# Fri3D_2018_POWER_00.net
KiCad netlist of a schematic drawn in Altium Designer
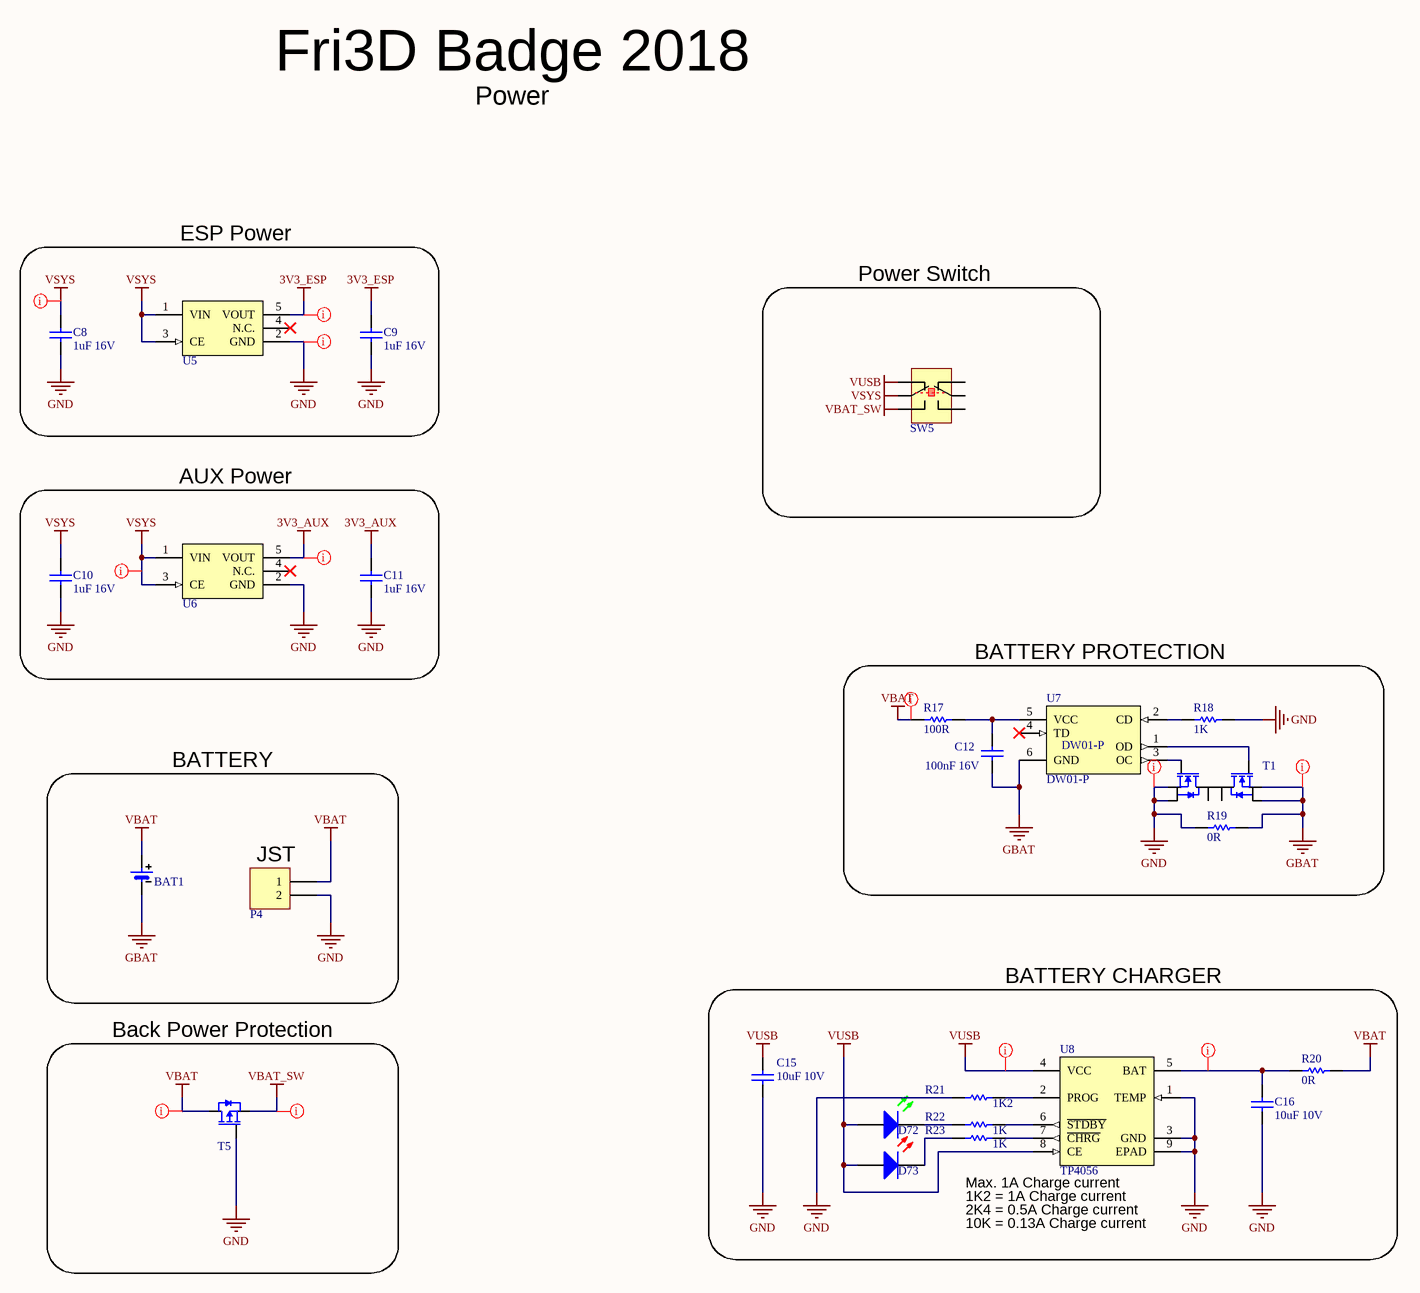
[diagram p0: Fri3D_2018_POWER_00.SchDoc]

(export (version "E")
  (design (tool "Eeschema 10.0.6"))
  (components
    (comp (ref "BAT1")
      (value "18650 Battery holder")
      (footprint "MPD_BH-18650-PC")
      (description "=Description")
      (libsource (lib "Phyx_Components") (part "BAT_2"))
    )
    (comp (ref "C8")
      (value "1uF 16V")
      (footprint "C0603_N")
      (description "Capacitor Ceramic")
      (fields (field (name "Comment") "CAP_CERAMIC"))
      (libsource (lib "Phyx_Components") (part "CAP_CERAMIC"))
    )
    (comp (ref "C9")
      (value "1uF 16V")
      (footprint "C0603_N")
      (description "Capacitor Ceramic")
      (fields (field (name "Comment") "CAP_CERAMIC"))
      (libsource (lib "Phyx_Components") (part "CAP_CERAMIC"))
    )
    (comp (ref "C10")
      (value "1uF 16V")
      (footprint "C0603_N")
      (description "Capacitor Ceramic")
      (fields (field (name "Comment") "CAP_CERAMIC"))
      (libsource (lib "Phyx_Components") (part "CAP_CERAMIC"))
    )
    (comp (ref "C11")
      (value "1uF 16V")
      (footprint "C0603_N")
      (description "Capacitor Ceramic")
      (fields (field (name "Comment") "CAP_CERAMIC"))
      (libsource (lib "Phyx_Components") (part "CAP_CERAMIC"))
    )
    (comp (ref "C12")
      (value "100nF 16V")
      (footprint "C0603_N")
      (description "Capacitor Ceramic")
      (libsource (lib "Phyx_Components") (part "CAP_CERAMIC"))
    )
    (comp (ref "C15")
      (value "10uF 10V")
      (footprint "C0805_N")
      (description "Capacitor Ceramic")
      (fields (field (name "Comment") "CAP_CERAMIC"))
      (libsource (lib "Phyx_Components") (part "CAP_CERAMIC"))
    )
    (comp (ref "C16")
      (value "10uF 10V")
      (footprint "C0805_N")
      (description "Capacitor Ceramic")
      (fields (field (name "Comment") "CAP_CERAMIC"))
      (libsource (lib "Phyx_Components") (part "CAP_CERAMIC"))
    )
    (comp (ref "D72")
      (value "Default 0805 Green LED")
      (footprint "LED_0805_GR")
      (description "=Description")
      (libsource (lib "Phyx_Components") (part "LED_GREEN"))
    )
    (comp (ref "D73")
      (value "Default 0805 Red LED")
      (footprint "LED_0805_RD")
      (description "=Description")
      (libsource (lib "Phyx_Components") (part "LED_RED"))
    )
    (comp (ref "P4")
      (value "Header 2.0mm Shrouded 2")
      (footprint "WE_620102131822")
      (libsource (lib "Phyx_Components") (part "Header 2"))
    )
    (comp (ref "R17")
      (value "100R")
      (footprint "R0603_N")
      (fields (field (name "Comment") "RESISTOR"))
      (libsource (lib "Phyx_Components") (part "RESISTOR"))
    )
    (comp (ref "R18")
      (value "1K")
      (footprint "R0603_N")
      (libsource (lib "Phyx_Components") (part "RESISTOR"))
    )
    (comp (ref "R19")
      (value "0R")
      (footprint "R0603_N")
      (libsource (lib "Phyx_Components") (part "RESISTOR"))
    )
    (comp (ref "R20")
      (value "0R")
      (footprint "R0603_N")
      (libsource (lib "Phyx_Components") (part "RESISTOR"))
    )
    (comp (ref "R21")
      (value "1K2")
      (footprint "R0603_N")
      (fields (field (name "Comment") "RESISTOR"))
      (libsource (lib "Phyx_Components") (part "RESISTOR"))
    )
    (comp (ref "R22")
      (value "1K")
      (footprint "R0603_N")
      (libsource (lib "Phyx_Components") (part "RESISTOR"))
    )
    (comp (ref "R23")
      (value "1K")
      (footprint "R0603_N")
      (libsource (lib "Phyx_Components") (part "RESISTOR"))
    )
    (comp (ref "SW5")
      (value "Mini slide switch 2P2T")
      (footprint "MSS22D18")
      (libsource (lib "Phyx_Components") (part "SW_2P2T"))
    )
    (comp (ref "T1")
      (value "Dual N-Ch MOSFET Common Drain")
      (footprint "TSSOP_8_65P")
      (description "=Description")
      (libsource (lib "Phyx_Components") (part "N_MOSFET_FS8205A"))
    )
    (comp (ref "T5")
      (value "3.1A P-Ch MOSFET Vgs -1v")
      (footprint "SOT23-3")
      (description "=Description")
      (libsource (lib "Phyx_Components") (part "P_MOSFET_GSD"))
    )
    (comp (ref "U5")
      (value "3V3 LDO 700mA 50mV")
      (footprint "SOT23-5")
      (description "=Designator")
      (libsource (lib "Phyx_Components") (part "XC6210_SOT"))
    )
    (comp (ref "U6")
      (value "3V3 LDO 700mA 50mV")
      (footprint "SOT23-5")
      (description "=Designator")
      (libsource (lib "Phyx_Components") (part "XC6210_SOT"))
    )
    (comp (ref "U7")
      (value "DW01-P")
      (footprint "SOT23-6")
      (description "=Description")
      (fields (field (name "Comment") "DW01-P single cell lithium protection"))
      (libsource (lib "Phyx_Components") (part "DW01-P"))
    )
    (comp (ref "U8")
      (value "TP4056")
      (footprint "SOIC_N_8_TH")
      (description "=Description")
      (fields (field (name "Comment") "Single Cell LiIon charger max 1A"))
      (libsource (lib "Phyx_Components") (part "TP4056"))
    )
  )
  (nets
    (net (code "1") (name "3V3_AUX") (class "Default")
      (node (ref "C11") (pin "1") (pinfunction "1_1") (pintype "passive"))
      (node (ref "U6") (pin "5") (pinfunction "VOUT_5") (pintype "power_in"))
    )
    (net (code "2") (name "3V3_ESP") (class "Default")
      (node (ref "C9") (pin "1") (pinfunction "1_1") (pintype "passive"))
      (node (ref "U5") (pin "5") (pinfunction "VOUT_5") (pintype "power_in"))
    )
    (net (code "3") (name "GBAT") (class "Default")
      (node (ref "BAT1") (pin "2") (pinfunction "2_2") (pintype "passive"))
      (node (ref "C12") (pin "2") (pinfunction "2_2") (pintype "passive"))
      (node (ref "R19") (pin "1") (pinfunction "1_1") (pintype "passive"))
      (node (ref "T1") (pin "2") (pinfunction "S1_2") (pintype "passive"))
      (node (ref "T1") (pin "3") (pinfunction "S1_3") (pintype "passive"))
      (node (ref "U7") (pin "6") (pinfunction "GND_6") (pintype "power_in"))
    )
    (net (code "4") (name "GND") (class "Default")
      (node (ref "C10") (pin "2") (pinfunction "2_2") (pintype "passive"))
      (node (ref "C11") (pin "2") (pinfunction "2_2") (pintype "passive"))
      (node (ref "C15") (pin "2") (pinfunction "2_2") (pintype "passive"))
      (node (ref "C16") (pin "2") (pinfunction "2_2") (pintype "passive"))
      (node (ref "C8") (pin "2") (pinfunction "2_2") (pintype "passive"))
      (node (ref "C9") (pin "2") (pinfunction "2_2") (pintype "passive"))
      (node (ref "P4") (pin "2") (pinfunction "2_2") (pintype "passive"))
      (node (ref "R18") (pin "2") (pinfunction "2_2") (pintype "passive"))
      (node (ref "R19") (pin "2") (pinfunction "2_2") (pintype "passive"))
      (node (ref "R21") (pin "2") (pinfunction "2_2") (pintype "passive"))
      (node (ref "T1") (pin "6") (pinfunction "S2_6") (pintype "passive"))
      (node (ref "T1") (pin "7") (pinfunction "S2_7") (pintype "passive"))
      (node (ref "T5") (pin "1") (pinfunction "G_1") (pintype "passive"))
      (node (ref "U5") (pin "2") (pinfunction "GND_2") (pintype "power_in"))
      (node (ref "U6") (pin "2") (pinfunction "GND_2") (pintype "power_in"))
      (node (ref "U8") (pin "1") (pinfunction "TEMP_1") (pintype "input"))
      (node (ref "U8") (pin "3") (pinfunction "GND_3") (pintype "power_in"))
      (node (ref "U8") (pin "9") (pinfunction "EPAD_9") (pintype "power_in"))
    )
    (net (code "5") (name "Net-(D72-K)") (class "Default")
      (node (ref "D72") (pin "2") (pinfunction "K_2") (pintype "passive"))
      (node (ref "R22") (pin "1") (pinfunction "1_1") (pintype "passive"))
    )
    (net (code "6") (name "Net-(D73-K)") (class "Default")
      (node (ref "D73") (pin "2") (pinfunction "K_2") (pintype "passive"))
      (node (ref "R23") (pin "1") (pinfunction "1_1") (pintype "passive"))
    )
    (net (code "7") (name "Net-(T1-G1)") (class "Default")
      (node (ref "T1") (pin "4") (pinfunction "G1_4") (pintype "passive"))
      (node (ref "U7") (pin "1") (pinfunction "OD_1") (pintype "output"))
    )
    (net (code "8") (name "Net-(T1-G2)") (class "Default")
      (node (ref "T1") (pin "5") (pinfunction "G2_5") (pintype "passive"))
      (node (ref "U7") (pin "3") (pinfunction "OC_3") (pintype "output"))
    )
    (net (code "9") (name "Net-(U7-CD)") (class "Default")
      (node (ref "R18") (pin "1") (pinfunction "1_1") (pintype "passive"))
      (node (ref "U7") (pin "2") (pinfunction "CD_2") (pintype "input"))
    )
    (net (code "10") (name "Net-(U7-VCC)") (class "Default")
      (node (ref "C12") (pin "1") (pinfunction "1_1") (pintype "passive"))
      (node (ref "R17") (pin "2") (pinfunction "2_2") (pintype "passive"))
      (node (ref "U7") (pin "5") (pinfunction "VCC_5") (pintype "power_in"))
    )
    (net (code "11") (name "Net-(U8-BAT)") (class "Default")
      (node (ref "C16") (pin "1") (pinfunction "1_1") (pintype "passive"))
      (node (ref "R20") (pin "2") (pinfunction "2_2") (pintype "passive"))
      (node (ref "U8") (pin "5") (pinfunction "BAT_5") (pintype "power_in"))
    )
    (net (code "12") (name "Net-(U8-PROG)") (class "Default")
      (node (ref "R21") (pin "1") (pinfunction "1_1") (pintype "passive"))
      (node (ref "U8") (pin "2") (pinfunction "PROG_2") (pintype "passive"))
    )
    (net (code "13") (name "Net-(U8-~{CHRG})") (class "Default")
      (node (ref "R23") (pin "2") (pinfunction "2_2") (pintype "passive"))
      (node (ref "U8") (pin "7") (pinfunction "~{CHRG}_7") (pintype "output"))
    )
    (net (code "14") (name "Net-(U8-~{STDBY})") (class "Default")
      (node (ref "R22") (pin "2") (pinfunction "2_2") (pintype "passive"))
      (node (ref "U8") (pin "6") (pinfunction "~{STDBY}_6") (pintype "output"))
    )
    (net (code "15") (name "VBAT") (class "Default")
      (node (ref "BAT1") (pin "1") (pinfunction "1_1") (pintype "passive"))
      (node (ref "P4") (pin "1") (pinfunction "1_1") (pintype "passive"))
      (node (ref "R17") (pin "1") (pinfunction "1_1") (pintype "passive"))
      (node (ref "R20") (pin "1") (pinfunction "1_1") (pintype "passive"))
      (node (ref "T5") (pin "3") (pinfunction "D_3") (pintype "passive"))
    )
    (net (code "16") (name "VBAT_SW") (class "Default")
      (node (ref "SW5") (pin "5") (pinfunction "5_5") (pintype "passive"))
      (node (ref "T5") (pin "2") (pinfunction "S_2") (pintype "passive"))
    )
    (net (code "17") (name "VSYS") (class "Default")
      (node (ref "C10") (pin "1") (pinfunction "1_1") (pintype "passive"))
      (node (ref "C8") (pin "1") (pinfunction "1_1") (pintype "passive"))
      (node (ref "SW5") (pin "3") (pinfunction "3_3") (pintype "passive"))
      (node (ref "U5") (pin "1") (pinfunction "VIN_1") (pintype "power_in"))
      (node (ref "U5") (pin "3") (pinfunction "CE_3") (pintype "input"))
      (node (ref "U6") (pin "1") (pinfunction "VIN_1") (pintype "power_in"))
      (node (ref "U6") (pin "3") (pinfunction "CE_3") (pintype "input"))
    )
    (net (code "18") (name "VUSB") (class "Default")
      (node (ref "C15") (pin "1") (pinfunction "1_1") (pintype "passive"))
      (node (ref "D72") (pin "1") (pinfunction "A_1") (pintype "passive"))
      (node (ref "D73") (pin "1") (pinfunction "A_1") (pintype "passive"))
      (node (ref "SW5") (pin "1") (pinfunction "1_1") (pintype "passive"))
      (node (ref "U8") (pin "4") (pinfunction "VCC_4") (pintype "power_in"))
      (node (ref "U8") (pin "8") (pinfunction "CE_8") (pintype "input"))
    )
    (net (code "19") (name "unconnected-(SW5-5-Pad6)") (class "Default")
      (node (ref "SW5") (pin "6") (pinfunction "5_6") (pintype "passive"))
    )
    (net (code "20") (name "unconnected-(SW5-Pad2)") (class "Default")
      (node (ref "SW5") (pin "2") (pinfunction "2_2") (pintype "passive"))
    )
    (net (code "21") (name "unconnected-(SW5-Pad4)") (class "Default")
      (node (ref "SW5") (pin "4") (pinfunction "4_4") (pintype "passive"))
    )
    (net (code "22") (name "unconnected-(T1-D1-Pad1)") (class "Default")
      (node (ref "T1") (pin "1") (pinfunction "D1_1") (pintype "passive"))
    )
    (net (code "23") (name "unconnected-(T1-D2-Pad8)") (class "Default")
      (node (ref "T1") (pin "8") (pinfunction "D2_8") (pintype "passive"))
    )
    (net (code "24") (name "unconnected-(U5-N.C.-Pad4)") (class "Default")
      (node (ref "U5") (pin "4") (pinfunction "N.C._4") (pintype "passive+no_connect"))
    )
    (net (code "25") (name "unconnected-(U6-N.C.-Pad4)") (class "Default")
      (node (ref "U6") (pin "4") (pinfunction "N.C._4") (pintype "passive+no_connect"))
    )
    (net (code "26") (name "unconnected-(U7-TD-Pad4)") (class "Default")
      (node (ref "U7") (pin "4") (pinfunction "TD_4") (pintype "input+no_connect"))
    )
  )
)
